# MiniBoard.net
KiCad netlist of a schematic drawn in EAGLE
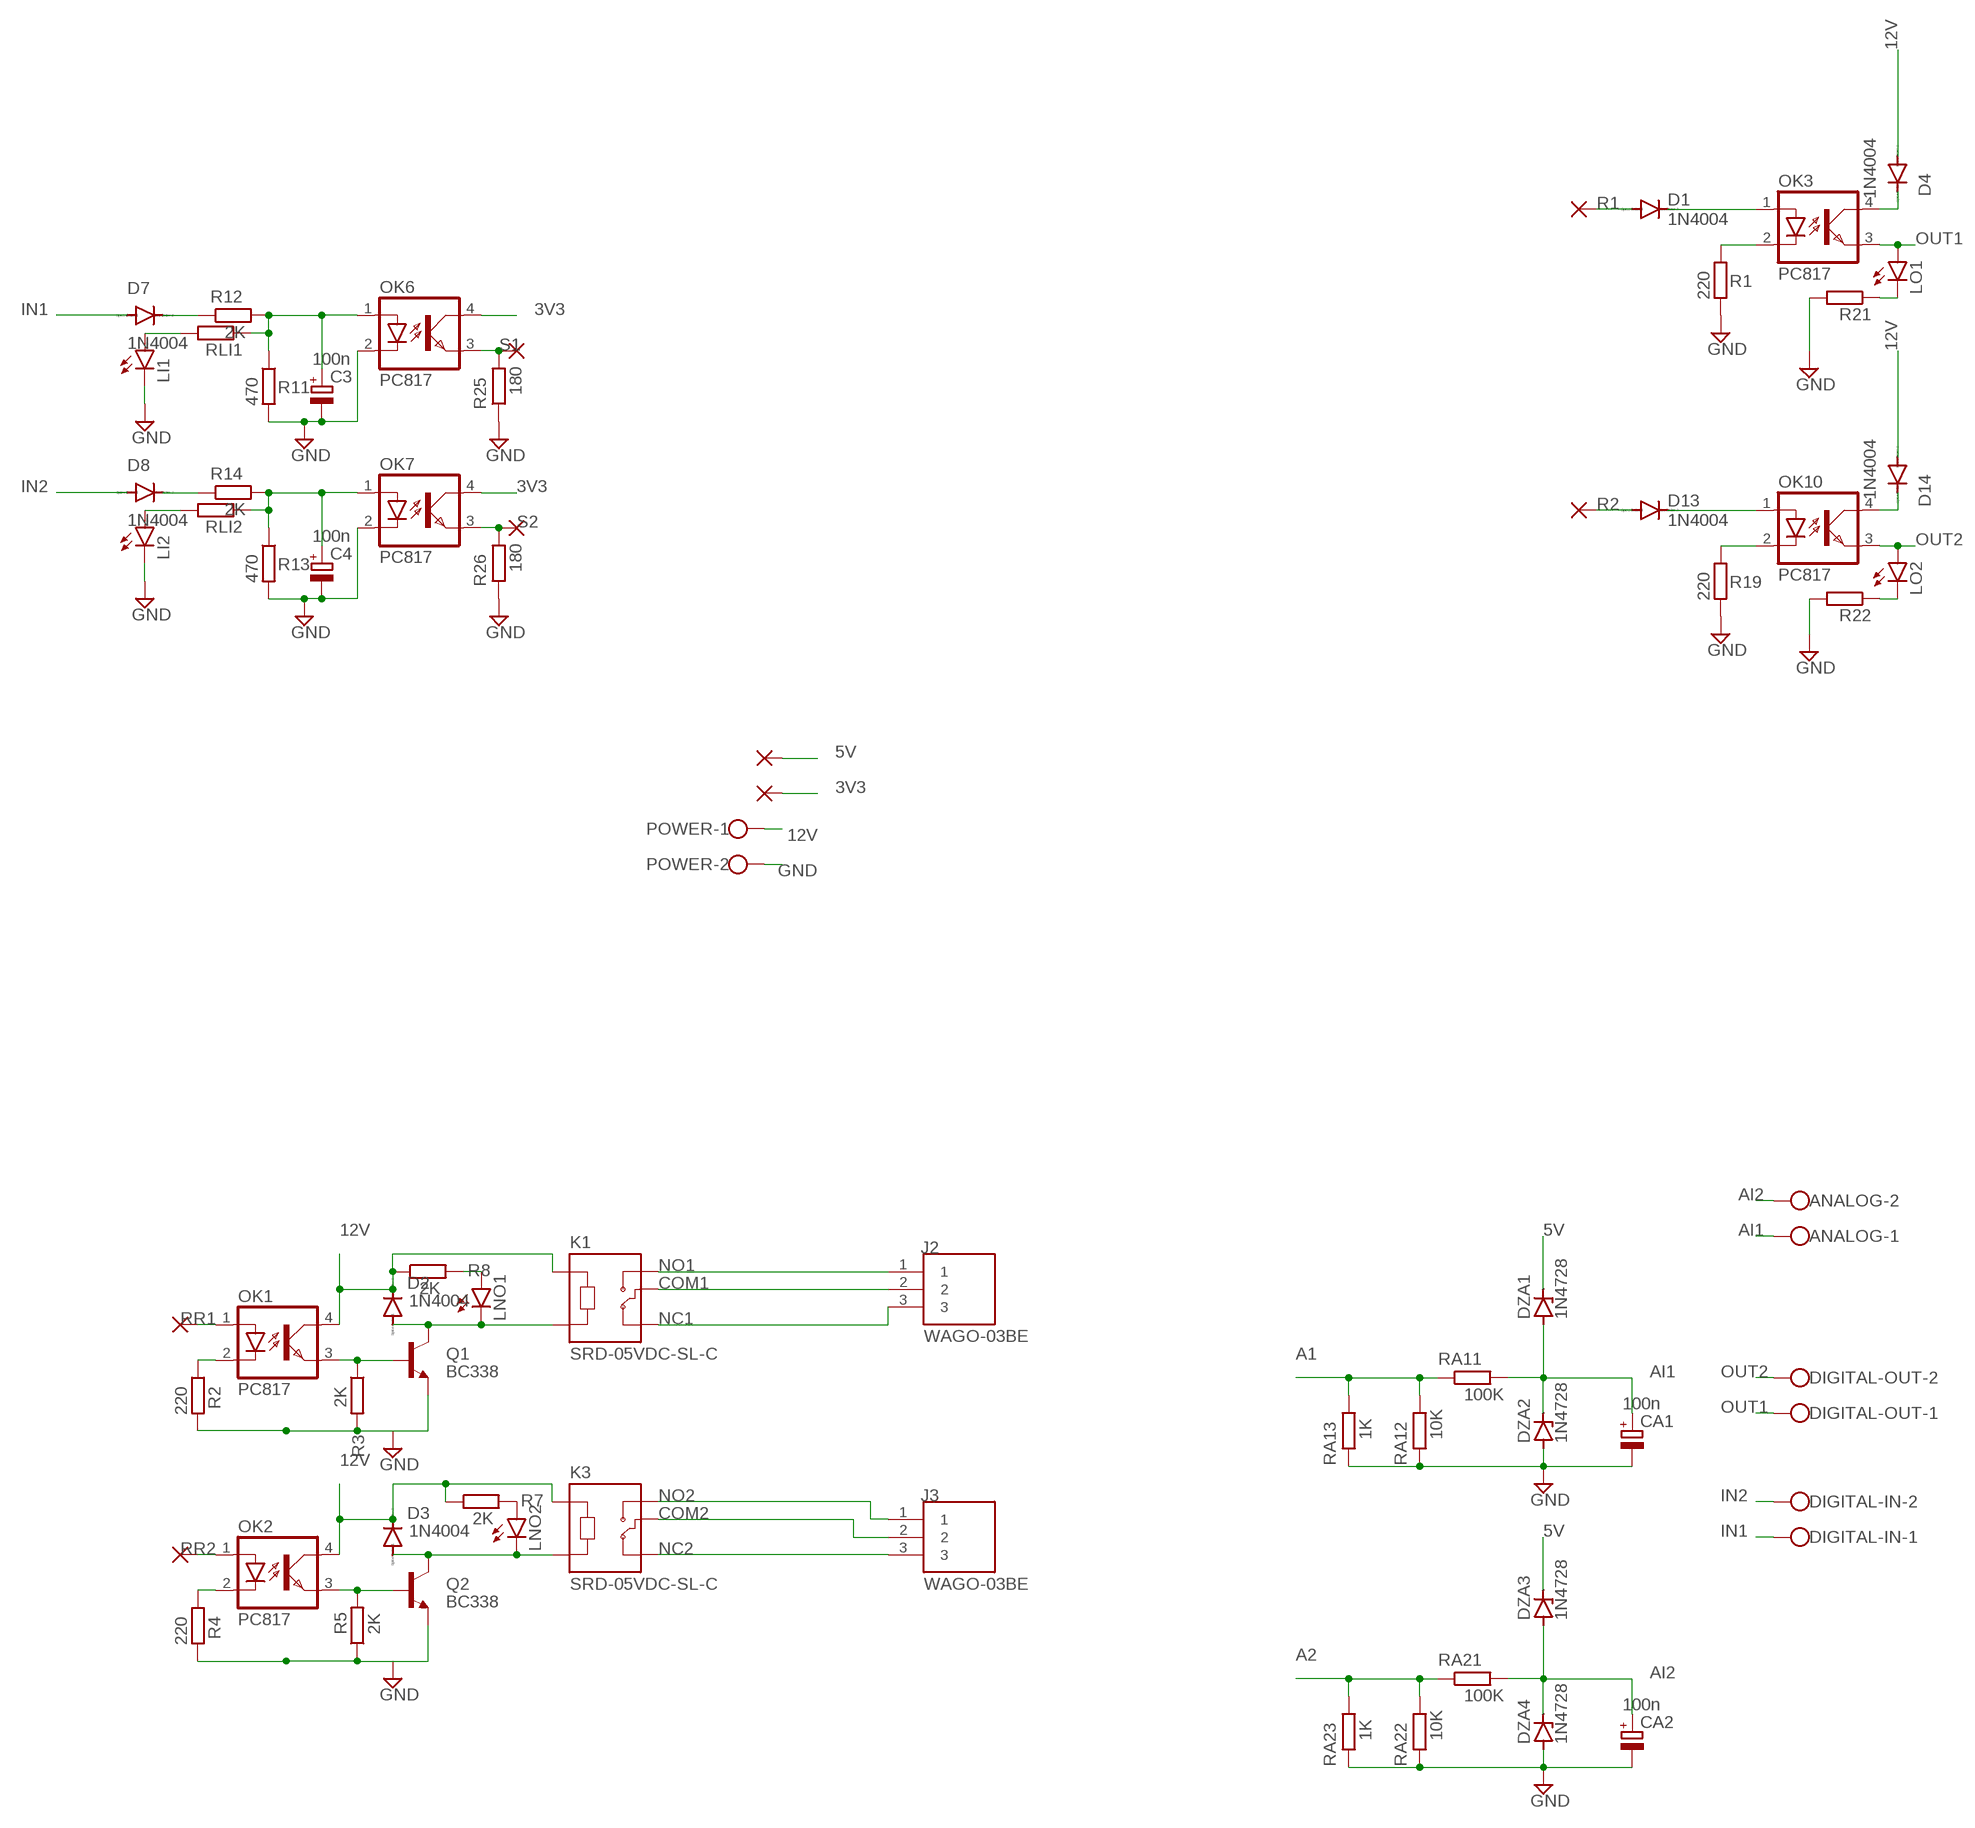
[diagram p0: schematic, sheet 1]

(export (version "E")
  (design (tool "Eeschema 10.0.6"))
  (components
    (comp (ref "ANALOG")
      (value "W237-102")
      (footprint "eagle-import:W237-102")
      (fields (field (name "MPN") "237-102"))
      (libsource (lib "eagle-import") (part "W237-102"))
    )
    (comp (ref "C3")
      (value "100n")
      (footprint "eagle-import:E5-6")
      (libsource (lib "eagle-import") (part "CPOL-EUE5-6"))
    )
    (comp (ref "C4")
      (value "100n")
      (footprint "eagle-import:E5-6")
      (libsource (lib "eagle-import") (part "CPOL-EUE5-6"))
    )
    (comp (ref "CA1")
      (value "100n")
      (footprint "eagle-import:E5-6")
      (libsource (lib "eagle-import") (part "CPOL-EUE5-6"))
    )
    (comp (ref "CA2")
      (value "100n")
      (footprint "eagle-import:E5-6")
      (libsource (lib "eagle-import") (part "CPOL-EUE5-6"))
    )
    (comp (ref "D1")
      (value "1N4004")
      (footprint "eagle-import:DO41-10")
      (libsource (lib "eagle-import") (part "1N4004"))
    )
    (comp (ref "D2")
      (value "1N4004")
      (footprint "eagle-import:DO41-10")
      (libsource (lib "eagle-import") (part "1N4004"))
    )
    (comp (ref "D3")
      (value "1N4004")
      (footprint "eagle-import:DO41-10")
      (libsource (lib "eagle-import") (part "1N4004"))
    )
    (comp (ref "D4")
      (value "1N4004")
      (footprint "eagle-import:DO41-10")
      (libsource (lib "eagle-import") (part "1N4004"))
    )
    (comp (ref "D7")
      (value "1N4004")
      (footprint "eagle-import:DO41-10")
      (libsource (lib "eagle-import") (part "1N4004"))
    )
    (comp (ref "D8")
      (value "1N4004")
      (footprint "eagle-import:DO41-10")
      (libsource (lib "eagle-import") (part "1N4004"))
    )
    (comp (ref "D13")
      (value "1N4004")
      (footprint "eagle-import:DO41-10")
      (libsource (lib "eagle-import") (part "1N4004"))
    )
    (comp (ref "D14")
      (value "1N4004")
      (footprint "eagle-import:DO41-10")
      (libsource (lib "eagle-import") (part "1N4004"))
    )
    (comp (ref "DIGITAL-IN")
      (value "W237-102")
      (footprint "eagle-import:W237-102")
      (fields (field (name "MPN") "237-102"))
      (libsource (lib "eagle-import") (part "W237-102"))
    )
    (comp (ref "DIGITAL-OUT")
      (value "W237-102")
      (footprint "eagle-import:W237-102")
      (fields (field (name "MPN") "237-102"))
      (libsource (lib "eagle-import") (part "W237-102"))
    )
    (comp (ref "DZA1")
      (value "1N4728")
      (footprint "eagle-import:DO41Z10")
      (libsource (lib "eagle-import") (part "1N4728"))
    )
    (comp (ref "DZA2")
      (value "1N4728")
      (footprint "eagle-import:DO41Z10")
      (libsource (lib "eagle-import") (part "1N4728"))
    )
    (comp (ref "DZA3")
      (value "1N4728")
      (footprint "eagle-import:DO41Z10")
      (libsource (lib "eagle-import") (part "1N4728"))
    )
    (comp (ref "DZA4")
      (value "1N4728")
      (footprint "eagle-import:DO41Z10")
      (libsource (lib "eagle-import") (part "1N4728"))
    )
    (comp (ref "J2")
      (value "WAGO-03BE")
      (footprint "eagle-import:CUI_TB006-508-03BE")
      (fields (field (name "MF") "Same Sky") (field (name "MP") "TB006-508-03BE"))
      (libsource (lib "eagle-import") (part "WAGO-03BE"))
    )
    (comp (ref "J3")
      (value "WAGO-03BE")
      (footprint "eagle-import:CUI_TB006-508-03BE")
      (fields (field (name "MF") "Same Sky") (field (name "MP") "TB006-508-03BE"))
      (libsource (lib "eagle-import") (part "WAGO-03BE"))
    )
    (comp (ref "K1")
      (value "SRD-05VDC-SL-C")
      (footprint "eagle-import:RELAY_SRD-05VDC-SL-C")
      (fields (field (name "MF") "Songle Relay"))
      (libsource (lib "eagle-import") (part "SRD-05VDC-SL-C"))
    )
    (comp (ref "K3")
      (value "SRD-05VDC-SL-C")
      (footprint "eagle-import:RELAY_SRD-05VDC-SL-C")
      (fields (field (name "MF") "Songle Relay"))
      (libsource (lib "eagle-import") (part "SRD-05VDC-SL-C"))
    )
    (comp (ref "LI1")
      (value "LED3MM")
      (footprint "eagle-import:LED3MM")
      (libsource (lib "eagle-import") (part "LED3MM"))
    )
    (comp (ref "LI2")
      (value "LED3MM")
      (footprint "eagle-import:LED3MM")
      (libsource (lib "eagle-import") (part "LED3MM"))
    )
    (comp (ref "LNO1")
      (value "LED3MM")
      (footprint "eagle-import:LED3MM")
      (libsource (lib "eagle-import") (part "LED3MM"))
    )
    (comp (ref "LNO2")
      (value "LED3MM")
      (footprint "eagle-import:LED3MM")
      (libsource (lib "eagle-import") (part "LED3MM"))
    )
    (comp (ref "LO1")
      (value "LED3MM")
      (footprint "eagle-import:LED3MM")
      (libsource (lib "eagle-import") (part "LED3MM"))
    )
    (comp (ref "LO2")
      (value "LED3MM")
      (footprint "eagle-import:LED3MM")
      (libsource (lib "eagle-import") (part "LED3MM"))
    )
    (comp (ref "OK1")
      (value "PC817")
      (footprint "eagle-import:DIL04")
      (fields (field (name "MPN") "PC817X4J000F"))
      (libsource (lib "eagle-import") (part "PC817"))
    )
    (comp (ref "OK2")
      (value "PC817")
      (footprint "eagle-import:DIL04")
      (fields (field (name "MPN") "PC817X4J000F"))
      (libsource (lib "eagle-import") (part "PC817"))
    )
    (comp (ref "OK3")
      (value "PC817")
      (footprint "eagle-import:DIL04")
      (fields (field (name "MPN") "PC817X4J000F"))
      (libsource (lib "eagle-import") (part "PC817"))
    )
    (comp (ref "OK6")
      (value "PC817")
      (footprint "eagle-import:DIL04")
      (fields (field (name "MPN") "PC817X4J000F"))
      (libsource (lib "eagle-import") (part "PC817"))
    )
    (comp (ref "OK7")
      (value "PC817")
      (footprint "eagle-import:DIL04")
      (fields (field (name "MPN") "PC817X4J000F"))
      (libsource (lib "eagle-import") (part "PC817"))
    )
    (comp (ref "OK10")
      (value "PC817")
      (footprint "eagle-import:DIL04")
      (fields (field (name "MPN") "PC817X4J000F"))
      (libsource (lib "eagle-import") (part "PC817"))
    )
    (comp (ref "PAD1")
      (value "WIREPAD1,6/0,9")
      (footprint "eagle-import:1,6_0,9")
      (libsource (lib "eagle-import") (part "WIREPAD1,6/0,9"))
    )
    (comp (ref "PAD2")
      (value "WIREPAD1,6/0,9")
      (footprint "eagle-import:1,6_0,9")
      (libsource (lib "eagle-import") (part "WIREPAD1,6/0,9"))
    )
    (comp (ref "PAD3")
      (value "WIREPAD1,6/0,9")
      (footprint "eagle-import:1,6_0,9")
      (libsource (lib "eagle-import") (part "WIREPAD1,6/0,9"))
    )
    (comp (ref "PAD4")
      (value "WIREPAD1,6/0,9")
      (footprint "eagle-import:1,6_0,9")
      (libsource (lib "eagle-import") (part "WIREPAD1,6/0,9"))
    )
    (comp (ref "PAD5")
      (value "WIREPAD1,6/0,9")
      (footprint "eagle-import:1,6_0,9")
      (libsource (lib "eagle-import") (part "WIREPAD1,6/0,9"))
    )
    (comp (ref "PAD6")
      (value "WIREPAD1,6/0,9")
      (footprint "eagle-import:1,6_0,9")
      (libsource (lib "eagle-import") (part "WIREPAD1,6/0,9"))
    )
    (comp (ref "PAD79")
      (value "WIREPAD1,6/0,9")
      (footprint "eagle-import:1,6_0,9")
      (libsource (lib "eagle-import") (part "WIREPAD1,6/0,9"))
    )
    (comp (ref "PAD80")
      (value "WIREPAD1,6/0,9")
      (footprint "eagle-import:1,6_0,9")
      (libsource (lib "eagle-import") (part "WIREPAD1,6/0,9"))
    )
    (comp (ref "POWER")
      (value "W237-102")
      (footprint "eagle-import:W237-102")
      (fields (field (name "MPN") "237-102"))
      (libsource (lib "eagle-import") (part "W237-102"))
    )
    (comp (ref "Q1")
      (value "BC338")
      (footprint "eagle-import:TO92-EBC")
      (libsource (lib "eagle-import") (part "BC338"))
    )
    (comp (ref "Q2")
      (value "BC338")
      (footprint "eagle-import:TO92-EBC")
      (libsource (lib "eagle-import") (part "BC338"))
    )
    (comp (ref "R1")
      (value "220")
      (footprint "eagle-import:0309_12")
      (libsource (lib "eagle-import") (part "R-EU_0309/12"))
    )
    (comp (ref "R2")
      (value "220")
      (footprint "eagle-import:0309_12")
      (libsource (lib "eagle-import") (part "R-EU_0309/12"))
    )
    (comp (ref "R3")
      (value "2K")
      (footprint "eagle-import:0309_12")
      (libsource (lib "eagle-import") (part "R-EU_0309/12"))
    )
    (comp (ref "R4")
      (value "220")
      (footprint "eagle-import:0309_12")
      (libsource (lib "eagle-import") (part "R-EU_0309/12"))
    )
    (comp (ref "R5")
      (value "2K")
      (footprint "eagle-import:0309_12")
      (libsource (lib "eagle-import") (part "R-EU_0309/12"))
    )
    (comp (ref "R7")
      (value "2K")
      (footprint "eagle-import:0309_12")
      (libsource (lib "eagle-import") (part "R-EU_0309/12"))
    )
    (comp (ref "R8")
      (value "2K")
      (footprint "eagle-import:0309_12")
      (libsource (lib "eagle-import") (part "R-EU_0309/12"))
    )
    (comp (ref "R11")
      (value "470")
      (footprint "eagle-import:0309_12")
      (libsource (lib "eagle-import") (part "R-EU_0309/12"))
    )
    (comp (ref "R12")
      (value "2K")
      (footprint "eagle-import:0309_12")
      (libsource (lib "eagle-import") (part "R-EU_0309/12"))
    )
    (comp (ref "R13")
      (value "470")
      (footprint "eagle-import:0309_12")
      (libsource (lib "eagle-import") (part "R-EU_0309/12"))
    )
    (comp (ref "R14")
      (value "2K")
      (footprint "eagle-import:0309_12")
      (libsource (lib "eagle-import") (part "R-EU_0309/12"))
    )
    (comp (ref "R19")
      (value "220")
      (footprint "eagle-import:0309_12")
      (libsource (lib "eagle-import") (part "R-EU_0309/12"))
    )
    (comp (ref "R21")
      (value "R-EU_0309/12")
      (footprint "eagle-import:0309_12")
      (libsource (lib "eagle-import") (part "R-EU_0309/12"))
    )
    (comp (ref "R22")
      (value "R-EU_0309/12")
      (footprint "eagle-import:0309_12")
      (libsource (lib "eagle-import") (part "R-EU_0309/12"))
    )
    (comp (ref "R25")
      (value "180")
      (footprint "eagle-import:0309_12")
      (libsource (lib "eagle-import") (part "R-EU_0309/12"))
    )
    (comp (ref "R26")
      (value "180")
      (footprint "eagle-import:0309_12")
      (libsource (lib "eagle-import") (part "R-EU_0309/12"))
    )
    (comp (ref "RA11")
      (value "100K")
      (footprint "eagle-import:0309_12")
      (libsource (lib "eagle-import") (part "R-EU_0309/12"))
    )
    (comp (ref "RA12")
      (value "10K")
      (footprint "eagle-import:0309_12")
      (libsource (lib "eagle-import") (part "R-EU_0309/12"))
    )
    (comp (ref "RA13")
      (value "1K")
      (footprint "eagle-import:0309_12")
      (libsource (lib "eagle-import") (part "R-EU_0309/12"))
    )
    (comp (ref "RA21")
      (value "100K")
      (footprint "eagle-import:0309_12")
      (libsource (lib "eagle-import") (part "R-EU_0309/12"))
    )
    (comp (ref "RA22")
      (value "10K")
      (footprint "eagle-import:0309_12")
      (libsource (lib "eagle-import") (part "R-EU_0309/12"))
    )
    (comp (ref "RA23")
      (value "1K")
      (footprint "eagle-import:0309_12")
      (libsource (lib "eagle-import") (part "R-EU_0309/12"))
    )
    (comp (ref "RLI1")
      (value "R-EU_0309/12")
      (footprint "eagle-import:0309_12")
      (libsource (lib "eagle-import") (part "R-EU_0309/12"))
    )
    (comp (ref "RLI2")
      (value "R-EU_0309/12")
      (footprint "eagle-import:0309_12")
      (libsource (lib "eagle-import") (part "R-EU_0309/12"))
    )
  )
  (nets
    (net (code "1") (name "/3V3") (class "Default")
      (node (ref "OK6") (pin "4") (pinfunction "COL_4") (pintype "passive"))
      (node (ref "OK7") (pin "4") (pinfunction "COL_4") (pintype "passive"))
      (node (ref "PAD5") (pin "1") (pinfunction "P_1") (pintype "passive"))
    )
    (net (code "2") (name "/5V") (class "Default")
      (node (ref "DZA1") (pin "C") (pinfunction "C_C") (pintype "passive"))
      (node (ref "DZA3") (pin "C") (pinfunction "C_C") (pintype "passive"))
      (node (ref "PAD6") (pin "1") (pinfunction "P_1") (pintype "passive"))
    )
    (net (code "3") (name "/12V") (class "Default")
      (node (ref "D14") (pin "A") (pinfunction "A_A") (pintype "passive"))
      (node (ref "D2") (pin "C") (pinfunction "C_C") (pintype "passive"))
      (node (ref "D3") (pin "C") (pinfunction "C_C") (pintype "passive"))
      (node (ref "D4") (pin "A") (pinfunction "A_A") (pintype "passive"))
      (node (ref "K1") (pin "A1") (pinfunction "A1_A1") (pintype "passive"))
      (node (ref "K3") (pin "A1") (pinfunction "A1_A1") (pintype "passive"))
      (node (ref "OK1") (pin "4") (pinfunction "COL_4") (pintype "passive"))
      (node (ref "OK2") (pin "4") (pinfunction "COL_4") (pintype "passive"))
      (node (ref "POWER") (pin "1") (pinfunction "KL_1") (pintype "passive"))
      (node (ref "R7") (pin "1") (pinfunction "1_1") (pintype "passive"))
      (node (ref "R8") (pin "1") (pinfunction "1_1") (pintype "passive"))
    )
    (net (code "4") (name "/A1") (class "Default")
      (node (ref "RA11") (pin "1") (pinfunction "1_1") (pintype "passive"))
      (node (ref "RA12") (pin "2") (pinfunction "2_2") (pintype "passive"))
      (node (ref "RA13") (pin "2") (pinfunction "2_2") (pintype "passive"))
    )
    (net (code "5") (name "/A2") (class "Default")
      (node (ref "RA21") (pin "1") (pinfunction "1_1") (pintype "passive"))
      (node (ref "RA22") (pin "2") (pinfunction "2_2") (pintype "passive"))
      (node (ref "RA23") (pin "2") (pinfunction "2_2") (pintype "passive"))
    )
    (net (code "6") (name "/AI1") (class "Default")
      (node (ref "ANALOG") (pin "1") (pinfunction "KL_1") (pintype "passive"))
      (node (ref "CA1") (pin "+") (pinfunction "+_+") (pintype "passive"))
      (node (ref "DZA1") (pin "A") (pinfunction "A_A") (pintype "passive"))
      (node (ref "DZA2") (pin "C") (pinfunction "C_C") (pintype "passive"))
      (node (ref "RA11") (pin "2") (pinfunction "2_2") (pintype "passive"))
    )
    (net (code "7") (name "/AI2") (class "Default")
      (node (ref "ANALOG") (pin "2") (pinfunction "KL_2") (pintype "passive"))
      (node (ref "CA2") (pin "+") (pinfunction "+_+") (pintype "passive"))
      (node (ref "DZA3") (pin "A") (pinfunction "A_A") (pintype "passive"))
      (node (ref "DZA4") (pin "C") (pinfunction "C_C") (pintype "passive"))
      (node (ref "RA21") (pin "2") (pinfunction "2_2") (pintype "passive"))
    )
    (net (code "8") (name "/COM1") (class "Default")
      (node (ref "J2") (pin "2") (pinfunction "2_2") (pintype "passive"))
      (node (ref "K1") (pin "COM") (pinfunction "COM_COM") (pintype "passive"))
    )
    (net (code "9") (name "/COM2") (class "Default")
      (node (ref "J3") (pin "2") (pinfunction "2_2") (pintype "passive"))
      (node (ref "K3") (pin "COM") (pinfunction "COM_COM") (pintype "passive"))
    )
    (net (code "10") (name "/IN1") (class "Default")
      (node (ref "D7") (pin "A") (pinfunction "A_A") (pintype "passive"))
      (node (ref "DIGITAL-IN") (pin "1") (pinfunction "KL_1") (pintype "passive"))
    )
    (net (code "11") (name "/IN2") (class "Default")
      (node (ref "D8") (pin "A") (pinfunction "A_A") (pintype "passive"))
      (node (ref "DIGITAL-IN") (pin "2") (pinfunction "KL_2") (pintype "passive"))
    )
    (net (code "12") (name "/NC1") (class "Default")
      (node (ref "J2") (pin "3") (pinfunction "3_3") (pintype "passive"))
      (node (ref "K1") (pin "NC") (pinfunction "NC_NC") (pintype "passive"))
    )
    (net (code "13") (name "/NC2") (class "Default")
      (node (ref "J3") (pin "3") (pinfunction "3_3") (pintype "passive"))
      (node (ref "K3") (pin "NC") (pinfunction "NC_NC") (pintype "passive"))
    )
    (net (code "14") (name "/NO1") (class "Default")
      (node (ref "J2") (pin "1") (pinfunction "1_1") (pintype "passive"))
      (node (ref "K1") (pin "NO") (pinfunction "NO_NO") (pintype "passive"))
    )
    (net (code "15") (name "/NO2") (class "Default")
      (node (ref "J3") (pin "1") (pinfunction "1_1") (pintype "passive"))
      (node (ref "K3") (pin "NO") (pinfunction "NO_NO") (pintype "passive"))
    )
    (net (code "16") (name "/OUT1") (class "Default")
      (node (ref "DIGITAL-OUT") (pin "1") (pinfunction "KL_1") (pintype "passive"))
      (node (ref "LO1") (pin "A") (pinfunction "A_A") (pintype "passive"))
      (node (ref "OK3") (pin "3") (pinfunction "EMIT_3") (pintype "passive"))
    )
    (net (code "17") (name "/OUT2") (class "Default")
      (node (ref "DIGITAL-OUT") (pin "2") (pinfunction "KL_2") (pintype "passive"))
      (node (ref "LO2") (pin "A") (pinfunction "A_A") (pintype "passive"))
      (node (ref "OK10") (pin "3") (pinfunction "EMIT_3") (pintype "passive"))
    )
    (net (code "18") (name "/R1") (class "Default")
      (node (ref "D1") (pin "A") (pinfunction "A_A") (pintype "passive"))
      (node (ref "PAD79") (pin "1") (pinfunction "P_1") (pintype "passive"))
    )
    (net (code "19") (name "/R2") (class "Default")
      (node (ref "D13") (pin "A") (pinfunction "A_A") (pintype "passive"))
      (node (ref "PAD80") (pin "1") (pinfunction "P_1") (pintype "passive"))
    )
    (net (code "20") (name "/RR1") (class "Default")
      (node (ref "OK1") (pin "1") (pinfunction "A_1") (pintype "passive"))
      (node (ref "PAD4") (pin "1") (pinfunction "P_1") (pintype "passive"))
    )
    (net (code "21") (name "/RR2") (class "Default")
      (node (ref "OK2") (pin "1") (pinfunction "A_1") (pintype "passive"))
      (node (ref "PAD3") (pin "1") (pinfunction "P_1") (pintype "passive"))
    )
    (net (code "22") (name "/S1") (class "Default")
      (node (ref "OK6") (pin "3") (pinfunction "EMIT_3") (pintype "passive"))
      (node (ref "PAD1") (pin "1") (pinfunction "P_1") (pintype "passive"))
      (node (ref "R25") (pin "2") (pinfunction "2_2") (pintype "passive"))
    )
    (net (code "23") (name "/S2") (class "Default")
      (node (ref "OK7") (pin "3") (pinfunction "EMIT_3") (pintype "passive"))
      (node (ref "PAD2") (pin "1") (pinfunction "P_1") (pintype "passive"))
      (node (ref "R26") (pin "2") (pinfunction "2_2") (pintype "passive"))
    )
    (net (code "24") (name "GND") (class "Default")
      (node (ref "C3") (pin "-") (pinfunction "-_-") (pintype "passive"))
      (node (ref "C4") (pin "-") (pinfunction "-_-") (pintype "passive"))
      (node (ref "CA1") (pin "-") (pinfunction "-_-") (pintype "passive"))
      (node (ref "CA2") (pin "-") (pinfunction "-_-") (pintype "passive"))
      (node (ref "DZA2") (pin "A") (pinfunction "A_A") (pintype "passive"))
      (node (ref "DZA4") (pin "A") (pinfunction "A_A") (pintype "passive"))
      (node (ref "LI1") (pin "K") (pinfunction "C_K") (pintype "passive"))
      (node (ref "LI2") (pin "K") (pinfunction "C_K") (pintype "passive"))
      (node (ref "OK6") (pin "2") (pinfunction "C_2") (pintype "passive"))
      (node (ref "OK7") (pin "2") (pinfunction "C_2") (pintype "passive"))
      (node (ref "POWER") (pin "2") (pinfunction "KL_2") (pintype "passive"))
      (node (ref "Q1") (pin "E") (pinfunction "E_E") (pintype "passive"))
      (node (ref "Q2") (pin "E") (pinfunction "E_E") (pintype "passive"))
      (node (ref "R1") (pin "2") (pinfunction "2_2") (pintype "passive"))
      (node (ref "R11") (pin "2") (pinfunction "2_2") (pintype "passive"))
      (node (ref "R13") (pin "2") (pinfunction "2_2") (pintype "passive"))
      (node (ref "R19") (pin "2") (pinfunction "2_2") (pintype "passive"))
      (node (ref "R2") (pin "2") (pinfunction "2_2") (pintype "passive"))
      (node (ref "R21") (pin "2") (pinfunction "2_2") (pintype "passive"))
      (node (ref "R22") (pin "2") (pinfunction "2_2") (pintype "passive"))
      (node (ref "R25") (pin "1") (pinfunction "1_1") (pintype "passive"))
      (node (ref "R26") (pin "1") (pinfunction "1_1") (pintype "passive"))
      (node (ref "R3") (pin "2") (pinfunction "2_2") (pintype "passive"))
      (node (ref "R4") (pin "2") (pinfunction "2_2") (pintype "passive"))
      (node (ref "R5") (pin "1") (pinfunction "1_1") (pintype "passive"))
      (node (ref "RA12") (pin "1") (pinfunction "1_1") (pintype "passive"))
      (node (ref "RA13") (pin "1") (pinfunction "1_1") (pintype "passive"))
      (node (ref "RA22") (pin "1") (pinfunction "1_1") (pintype "passive"))
      (node (ref "RA23") (pin "1") (pinfunction "1_1") (pintype "passive"))
    )
    (net (code "25") (name "Net-(D7-PadC)") (class "Default")
      (node (ref "D7") (pin "C") (pinfunction "C_C") (pintype "passive"))
      (node (ref "R12") (pin "1") (pinfunction "1_1") (pintype "passive"))
    )
    (net (code "26") (name "Net-(D8-PadC)") (class "Default")
      (node (ref "D8") (pin "C") (pinfunction "C_C") (pintype "passive"))
      (node (ref "R14") (pin "1") (pinfunction "1_1") (pintype "passive"))
    )
    (net (code "27") (name "Net-(LI1-PadA)") (class "Default")
      (node (ref "LI1") (pin "A") (pinfunction "A_A") (pintype "passive"))
      (node (ref "RLI1") (pin "2") (pinfunction "2_2") (pintype "passive"))
    )
    (net (code "28") (name "Net-(LI2-PadA)") (class "Default")
      (node (ref "LI2") (pin "A") (pinfunction "A_A") (pintype "passive"))
      (node (ref "RLI2") (pin "2") (pinfunction "2_2") (pintype "passive"))
    )
    (net (code "29") (name "Net-(LNO1-C)") (class "Default")
      (node (ref "D2") (pin "A") (pinfunction "A_A") (pintype "passive"))
      (node (ref "K1") (pin "A2") (pinfunction "A2_A2") (pintype "passive"))
      (node (ref "LNO1") (pin "K") (pinfunction "C_K") (pintype "passive"))
      (node (ref "Q1") (pin "C") (pinfunction "C_C") (pintype "passive"))
    )
    (net (code "30") (name "Net-(LNO1-PadA)") (class "Default")
      (node (ref "LNO1") (pin "A") (pinfunction "A_A") (pintype "passive"))
      (node (ref "R8") (pin "2") (pinfunction "2_2") (pintype "passive"))
    )
    (net (code "31") (name "Net-(LNO2-C)") (class "Default")
      (node (ref "D3") (pin "A") (pinfunction "A_A") (pintype "passive"))
      (node (ref "K3") (pin "A2") (pinfunction "A2_A2") (pintype "passive"))
      (node (ref "LNO2") (pin "K") (pinfunction "C_K") (pintype "passive"))
      (node (ref "Q2") (pin "C") (pinfunction "C_C") (pintype "passive"))
    )
    (net (code "32") (name "Net-(LNO2-PadA)") (class "Default")
      (node (ref "LNO2") (pin "A") (pinfunction "A_A") (pintype "passive"))
      (node (ref "R7") (pin "2") (pinfunction "2_2") (pintype "passive"))
    )
    (net (code "33") (name "Net-(LO1-C)") (class "Default")
      (node (ref "LO1") (pin "K") (pinfunction "C_K") (pintype "passive"))
      (node (ref "R21") (pin "1") (pinfunction "1_1") (pintype "passive"))
    )
    (net (code "34") (name "Net-(LO2-C)") (class "Default")
      (node (ref "LO2") (pin "K") (pinfunction "C_K") (pintype "passive"))
      (node (ref "R22") (pin "1") (pinfunction "1_1") (pintype "passive"))
    )
    (net (code "35") (name "Net-(OK1-C)") (class "Default")
      (node (ref "OK1") (pin "2") (pinfunction "C_2") (pintype "passive"))
      (node (ref "R2") (pin "1") (pinfunction "1_1") (pintype "passive"))
    )
    (net (code "36") (name "Net-(OK1-EMIT)") (class "Default")
      (node (ref "OK1") (pin "3") (pinfunction "EMIT_3") (pintype "passive"))
      (node (ref "Q1") (pin "B") (pinfunction "B_B") (pintype "passive"))
      (node (ref "R3") (pin "1") (pinfunction "1_1") (pintype "passive"))
    )
    (net (code "37") (name "Net-(OK2-C)") (class "Default")
      (node (ref "OK2") (pin "2") (pinfunction "C_2") (pintype "passive"))
      (node (ref "R4") (pin "1") (pinfunction "1_1") (pintype "passive"))
    )
    (net (code "38") (name "Net-(OK2-EMIT)") (class "Default")
      (node (ref "OK2") (pin "3") (pinfunction "EMIT_3") (pintype "passive"))
      (node (ref "Q2") (pin "B") (pinfunction "B_B") (pintype "passive"))
      (node (ref "R5") (pin "2") (pinfunction "2_2") (pintype "passive"))
    )
    (net (code "39") (name "Net-(OK3-A)") (class "Default")
      (node (ref "D1") (pin "C") (pinfunction "C_C") (pintype "passive"))
      (node (ref "OK3") (pin "1") (pinfunction "A_1") (pintype "passive"))
    )
    (net (code "40") (name "Net-(OK3-C)") (class "Default")
      (node (ref "OK3") (pin "2") (pinfunction "C_2") (pintype "passive"))
      (node (ref "R1") (pin "1") (pinfunction "1_1") (pintype "passive"))
    )
    (net (code "41") (name "Net-(OK3-COL)") (class "Default")
      (node (ref "D4") (pin "C") (pinfunction "C_C") (pintype "passive"))
      (node (ref "OK3") (pin "4") (pinfunction "COL_4") (pintype "passive"))
    )
    (net (code "42") (name "Net-(OK6-A)") (class "Default")
      (node (ref "C3") (pin "+") (pinfunction "+_+") (pintype "passive"))
      (node (ref "OK6") (pin "1") (pinfunction "A_1") (pintype "passive"))
      (node (ref "R11") (pin "1") (pinfunction "1_1") (pintype "passive"))
      (node (ref "R12") (pin "2") (pinfunction "2_2") (pintype "passive"))
      (node (ref "RLI1") (pin "1") (pinfunction "1_1") (pintype "passive"))
    )
    (net (code "43") (name "Net-(OK7-A)") (class "Default")
      (node (ref "C4") (pin "+") (pinfunction "+_+") (pintype "passive"))
      (node (ref "OK7") (pin "1") (pinfunction "A_1") (pintype "passive"))
      (node (ref "R13") (pin "1") (pinfunction "1_1") (pintype "passive"))
      (node (ref "R14") (pin "2") (pinfunction "2_2") (pintype "passive"))
      (node (ref "RLI2") (pin "1") (pinfunction "1_1") (pintype "passive"))
    )
    (net (code "44") (name "Net-(OK10-A)") (class "Default")
      (node (ref "D13") (pin "C") (pinfunction "C_C") (pintype "passive"))
      (node (ref "OK10") (pin "1") (pinfunction "A_1") (pintype "passive"))
    )
    (net (code "45") (name "Net-(OK10-C)") (class "Default")
      (node (ref "OK10") (pin "2") (pinfunction "C_2") (pintype "passive"))
      (node (ref "R19") (pin "1") (pinfunction "1_1") (pintype "passive"))
    )
    (net (code "46") (name "Net-(OK10-COL)") (class "Default")
      (node (ref "D14") (pin "C") (pinfunction "C_C") (pintype "passive"))
      (node (ref "OK10") (pin "4") (pinfunction "COL_4") (pintype "passive"))
    )
  )
)
